# wemos_temp.net
KiCad netlist of a schematic drawn in EAGLE
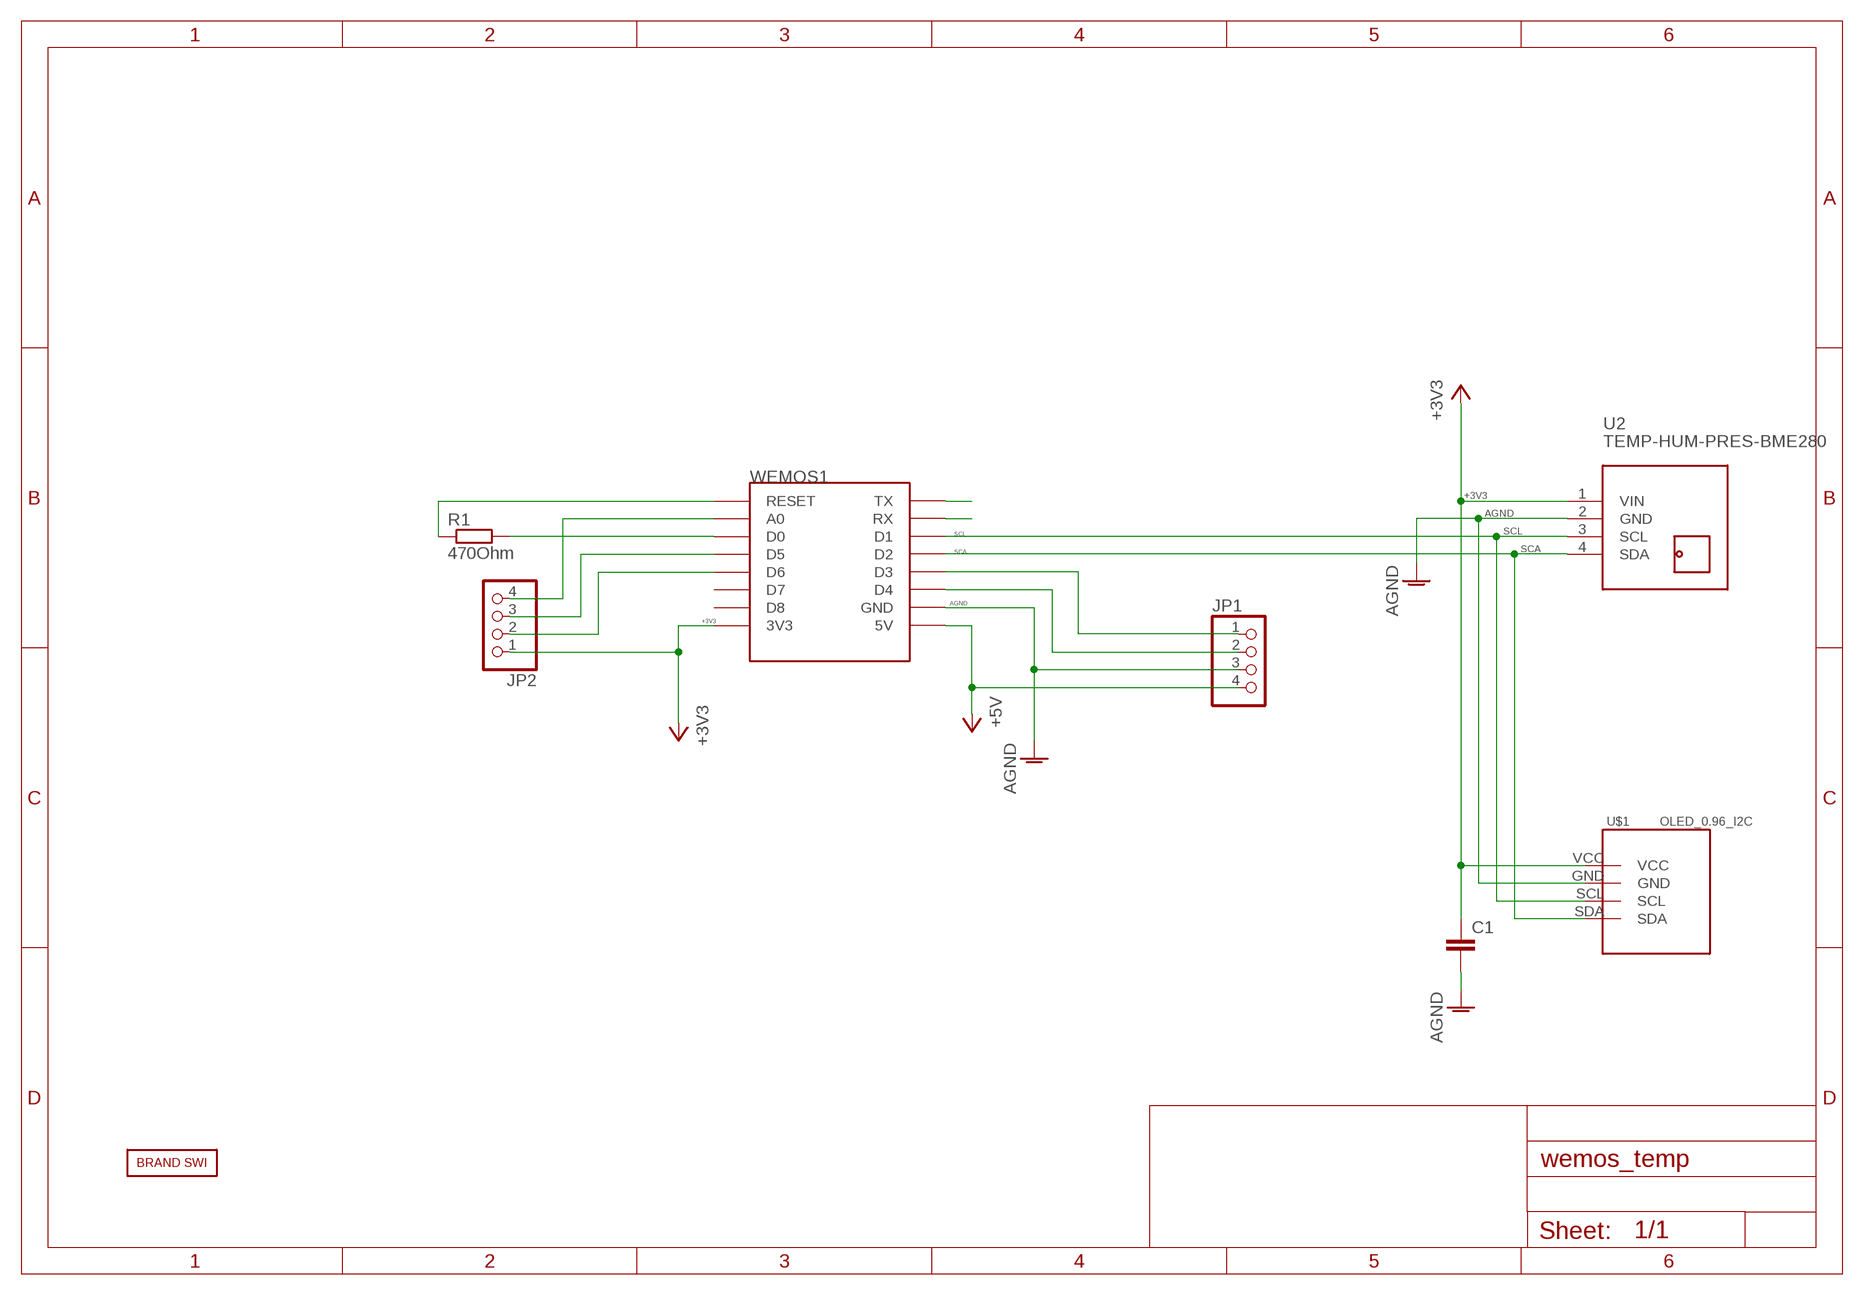
[diagram p0: schematic, sheet 1]

(export (version "E")
  (design (tool "Eeschema 10.0.6"))
  (components
    (comp (ref "C1")
      (value "C-EUC1210")
      (footprint "eagle-import:C1210")
      (libsource (lib "eagle-import") (part "C-EUC1210"))
    )
    (comp (ref "JP1")
      (value "PINHD-1X4")
      (footprint "eagle-import:1X04")
      (libsource (lib "eagle-import") (part "PINHD-1X4"))
    )
    (comp (ref "JP2")
      (value "PINHD-1X4")
      (footprint "eagle-import:1X04")
      (libsource (lib "eagle-import") (part "PINHD-1X4"))
    )
    (comp (ref "R1")
      (value "470Ohm")
      (footprint "eagle-import:R0805")
      (libsource (lib "eagle-import") (part "R-EU_R0805"))
    )
    (comp (ref "U$1")
      (value "OLED_0.96_I2C")
      (footprint "eagle-import:OLED_0.96_I2C")
      (libsource (lib "eagle-import") (part "OLED_0.96_I2C"))
    )
    (comp (ref "U$2")
      (value "BRAND_SWI5X7")
      (footprint "eagle-import:BRAND_SWI_5X7")
      (libsource (lib "eagle-import") (part "BRAND_SWI5X7"))
    )
    (comp (ref "U2")
      (value "TEMP-HUM-PRES-BME280")
      (footprint "eagle-import:TEMP-HUM-PRES-BME280")
      (libsource (lib "eagle-import") (part "TEMP-HUM-PRES-BME280"))
    )
    (comp (ref "WEMOS1")
      (value "WEMOS-D1-MINI")
      (footprint "eagle-import:WEMOS-D1-MINI")
      (libsource (lib "eagle-import") (part "WEMOS-D1-MINI"))
    )
  )
  (nets
    (net (code "1") (name "+3V3") (class "Default")
      (node (ref "C1") (pin "1") (pinfunction "1_1") (pintype "passive"))
      (node (ref "JP2") (pin "1") (pinfunction "1_1") (pintype "passive"))
      (node (ref "U$1") (pin "VCC") (pinfunction "VCC_VCC") (pintype "bidirectional"))
      (node (ref "U2") (pin "1") (pinfunction "VIN_1") (pintype "power_in"))
      (node (ref "WEMOS1") (pin "3V3") (pinfunction "3V3_3V3") (pintype "bidirectional"))
    )
    (net (code "2") (name "+5V") (class "Default")
      (node (ref "JP1") (pin "4") (pinfunction "4_4") (pintype "passive"))
      (node (ref "WEMOS1") (pin "5V") (pinfunction "5V_5V") (pintype "bidirectional"))
    )
    (net (code "3") (name "/SCA") (class "Default")
      (node (ref "U$1") (pin "SDA") (pinfunction "SDA_SDA") (pintype "bidirectional"))
      (node (ref "U2") (pin "4") (pinfunction "SDA_4") (pintype "bidirectional"))
      (node (ref "WEMOS1") (pin "D2") (pinfunction "D2_D2") (pintype "bidirectional"))
    )
    (net (code "4") (name "/SCL") (class "Default")
      (node (ref "U$1") (pin "SCL") (pinfunction "SCL_SCL") (pintype "bidirectional"))
      (node (ref "U2") (pin "3") (pinfunction "SCL_3") (pintype "bidirectional"))
      (node (ref "WEMOS1") (pin "D1") (pinfunction "D1_D1") (pintype "bidirectional"))
    )
    (net (code "5") (name "AGND") (class "Default")
      (node (ref "C1") (pin "2") (pinfunction "2_2") (pintype "passive"))
      (node (ref "JP1") (pin "3") (pinfunction "3_3") (pintype "passive"))
      (node (ref "U$1") (pin "GND") (pinfunction "GND_GND") (pintype "bidirectional"))
      (node (ref "U2") (pin "2") (pinfunction "GND_2") (pintype "power_in"))
      (node (ref "WEMOS1") (pin "GND") (pinfunction "GND_GND") (pintype "bidirectional"))
    )
    (net (code "6") (name "Net-(JP1-Pad1)") (class "Default")
      (node (ref "JP1") (pin "1") (pinfunction "1_1") (pintype "passive"))
      (node (ref "WEMOS1") (pin "D3") (pinfunction "D3_D3") (pintype "bidirectional"))
    )
    (net (code "7") (name "Net-(JP1-Pad2)") (class "Default")
      (node (ref "JP1") (pin "2") (pinfunction "2_2") (pintype "passive"))
      (node (ref "WEMOS1") (pin "D4") (pinfunction "D4_D4") (pintype "bidirectional"))
    )
    (net (code "8") (name "Net-(JP2-Pad2)") (class "Default")
      (node (ref "JP2") (pin "2") (pinfunction "2_2") (pintype "passive"))
      (node (ref "WEMOS1") (pin "D6") (pinfunction "D6_D6") (pintype "bidirectional"))
    )
    (net (code "9") (name "Net-(JP2-Pad3)") (class "Default")
      (node (ref "JP2") (pin "3") (pinfunction "3_3") (pintype "passive"))
      (node (ref "WEMOS1") (pin "D5") (pinfunction "D5_D5") (pintype "bidirectional"))
    )
    (net (code "10") (name "Net-(JP2-Pad4)") (class "Default")
      (node (ref "JP2") (pin "4") (pinfunction "4_4") (pintype "passive"))
      (node (ref "WEMOS1") (pin "A0") (pinfunction "A0_A0") (pintype "bidirectional"))
    )
    (net (code "11") (name "Net-(R1-Pad1)") (class "Default")
      (node (ref "R1") (pin "1") (pinfunction "1_1") (pintype "passive"))
      (node (ref "WEMOS1") (pin "RESET") (pinfunction "RESET_RESET") (pintype "bidirectional"))
    )
    (net (code "12") (name "Net-(R1-Pad2)") (class "Default")
      (node (ref "R1") (pin "2") (pinfunction "2_2") (pintype "passive"))
      (node (ref "WEMOS1") (pin "D0") (pinfunction "D0_D0") (pintype "bidirectional"))
    )
    (net (code "13") (name "unconnected-(WEMOS1-PadD7)") (class "Default")
      (node (ref "WEMOS1") (pin "D7") (pinfunction "D7_D7") (pintype "bidirectional"))
    )
    (net (code "14") (name "unconnected-(WEMOS1-PadD8)") (class "Default")
      (node (ref "WEMOS1") (pin "D8") (pinfunction "D8_D8") (pintype "bidirectional"))
    )
    (net (code "15") (name "unconnected-(WEMOS1-PadRX)") (class "Default")
      (node (ref "WEMOS1") (pin "RX") (pinfunction "RX_RX") (pintype "bidirectional"))
    )
    (net (code "16") (name "unconnected-(WEMOS1-PadTX)") (class "Default")
      (node (ref "WEMOS1") (pin "TX") (pinfunction "TX_TX") (pintype "bidirectional"))
    )
  )
)
